# POWER_SUPPLY.net
KiCad netlist of a schematic drawn in Altium Designer
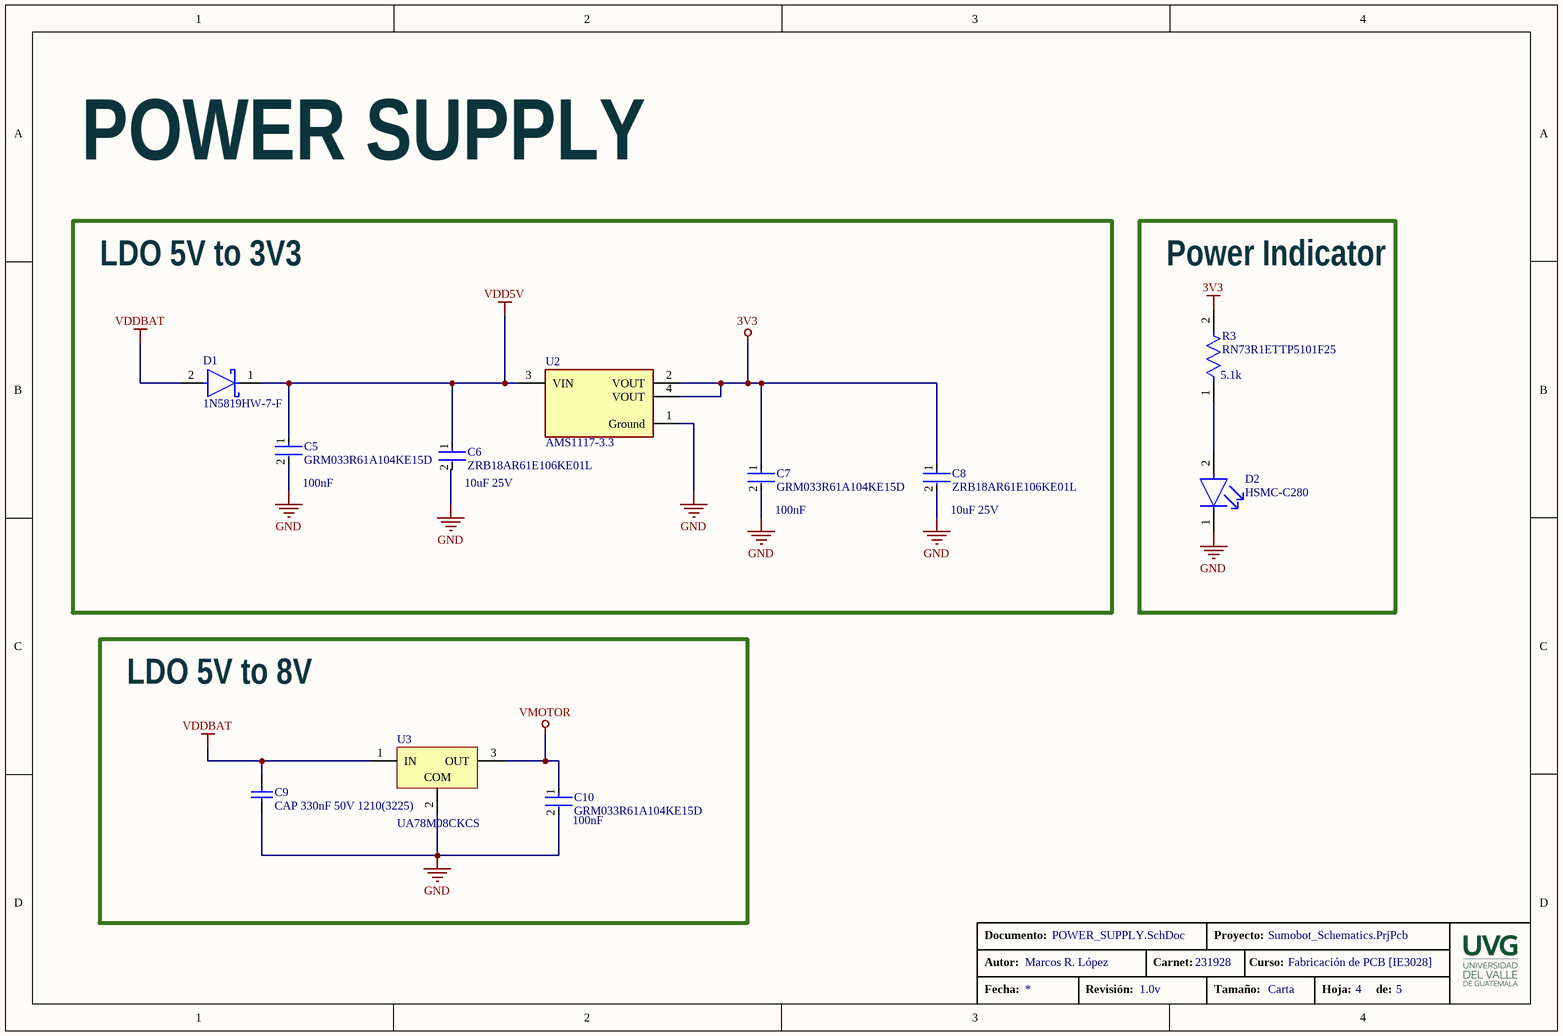
[diagram p0: POWER_SUPPLY.SchDoc]

(export (version "E")
  (design (tool "Eeschema 10.0.6"))
  (components
    (comp (ref "C5")
      (value "GRM033R61A104KE15D")
      (footprint "FP-GRM033-0_03-IPC_C")
      (description "Chip Multilayer Ceramic Capacitors for General Purpose, 0201, 0.10uF, X5R, 15%, 10%, 10V")
      (fields
        (field (name "TOLERANCE") "10%")
        (field (name "CAPACITANCE") "100nF")
        (field (name "VOLTAGE") "10V")
      )
      (libsource (lib "Altium Content Vault") (part "b4654b650e69147ec39a6b967a45e02"))
    )
    (comp (ref "C6")
      (value "ZRB18AR61E106KE01L")
      (footprint "FP-ZRB18A-0_2-MFG")
      (fields (field (name "ALTIUM_VALUE") "10uF 25V"))
      (libsource (lib "Altium Content Vault") (part "02cd4be3c70576c341d710602a673aa"))
    )
    (comp (ref "C7")
      (value "GRM033R61A104KE15D")
      (footprint "FP-GRM033-0_03-IPC_C")
      (description "Chip Multilayer Ceramic Capacitors for General Purpose, 0201, 0.10uF, X5R, 15%, 10%, 10V")
      (fields
        (field (name "TOLERANCE") "10%")
        (field (name "CAPACITANCE") "100nF")
        (field (name "VOLTAGE") "10V")
      )
      (libsource (lib "Altium Content Vault") (part "b4654b650e69147ec39a6b967a45e02"))
    )
    (comp (ref "C8")
      (value "ZRB18AR61E106KE01L")
      (footprint "FP-ZRB18A-0_2-MFG")
      (fields (field (name "ALTIUM_VALUE") "10uF 25V"))
      (libsource (lib "Altium Content Vault") (part "02cd4be3c70576c341d710602a673aa"))
    )
    (comp (ref "C9")
      (value "CAP 330nF 50V 1210(3225)")
      (footprint "CAPC1210(3225)105_L")
      (description "CAP 330nF 50V ±10% 1210 (3225 Metric) Thickness 1.05mm SMD")
      (fields (field (name "TOLERANCE") "Â±10%"))
      (libsource (lib "Altium Content Vault") (part "CAP"))
    )
    (comp (ref "C10")
      (value "GRM033R61A104KE15D")
      (footprint "FP-GRM033-0_03-IPC_C")
      (description "Chip Multilayer Ceramic Capacitors for General Purpose, 0201, 0.10uF, X5R, 15%, 10%, 10V")
      (fields
        (field (name "TOLERANCE") "10%")
        (field (name "CAPACITANCE") "100nF")
        (field (name "VOLTAGE") "10V")
      )
      (libsource (lib "Altium Content Vault") (part "b4654b650e69147ec39a6b967a45e02"))
    )
    (comp (ref "D1")
      (value "1N5819HW-7-F")
      (footprint "FP-SOD123-IPC_A")
      (description "DIODE SCHOTTKY 40V 1A SOD123")
      (libsource (lib "Altium Content Vault") (part "1d6ec82d83fb6aee721767c19dac4b9"))
    )
    (comp (ref "D2")
      (value "HSMC-C280")
      (footprint "FP-HSMC-C280-MFG")
      (description "LED RED DIFFUSED 0402 SMD")
      (libsource (lib "Altium Content Vault") (part "8706943c75ba83719d021d2fdc84c58"))
    )
    (comp (ref "R3")
      (value "RN73R1ETTP5101F25")
      (footprint "FP-RN73R1E-IPC_C")
      (description "5.1kΩ ±1% 0.063W, 1/16W Chip Resistor 0402 (1005 Metric) Moisture Resistant Thin Film")
      (fields (field (name "ALTIUM_VALUE") "5.1k"))
      (libsource (lib "Altium Content Vault") (part "1029c3af85768c4190bb7ad29bc67b5"))
    )
    (comp (ref "U2")
      (value "AMS1117-3.3")
      (footprint "FP-AMS1117-IPC_C")
      (description "LDO Voltage Regulators 1A, 3.3V")
      (fields
        (field (name "OCTOPART") "https://octopart.com/ams1117-3.3-advanced+monolithic+systems-25899300")
        (field (name "MANUFACTURER") "Advanced Monolithic Systems")
      )
      (libsource (lib "Altium Content Vault") (part "8bdbb5f8e77002000e30dd2845d0354"))
    )
    (comp (ref "U3")
      (value "UA78M08CKCS")
      (footprint "KCS0003A")
      (fields (field (name "MANUFACTURER") "Texas Instruments"))
      (libsource (lib "Altium Content Vault") (part "TI-UA78M08KCS3"))
    )
  )
  (nets
    (net (code "1") (name "3V3") (class "Default")
      (node (ref "C7") (pin "1") (pinfunction "1_1") (pintype "passive"))
      (node (ref "C8") (pin "1") (pinfunction "1_1") (pintype "passive"))
      (node (ref "R3") (pin "2") (pinfunction "2_2") (pintype "passive"))
      (node (ref "U2") (pin "2") (pinfunction "VOUT_2") (pintype "passive"))
      (node (ref "U2") (pin "4") (pinfunction "VOUT_4") (pintype "passive"))
    )
    (net (code "2") (name "GND") (class "Default")
      (node (ref "C10") (pin "2") (pinfunction "2_2") (pintype "passive"))
      (node (ref "C5") (pin "2") (pinfunction "2_2") (pintype "passive"))
      (node (ref "C6") (pin "2") (pinfunction "2_2") (pintype "passive"))
      (node (ref "C7") (pin "2") (pinfunction "2_2") (pintype "passive"))
      (node (ref "C8") (pin "2") (pinfunction "2_2") (pintype "passive"))
      (node (ref "C9") (pin "1") (pinfunction "1_1") (pintype "passive"))
      (node (ref "D2") (pin "1") (pinfunction "C_1") (pintype "passive"))
      (node (ref "U2") (pin "1") (pinfunction "Ground_1") (pintype "power_in"))
      (node (ref "U3") (pin "2") (pinfunction "COM_2") (pintype "power_in"))
    )
    (net (code "3") (name "Net-(D2-A)") (class "Default")
      (node (ref "D2") (pin "2") (pinfunction "A_2") (pintype "passive"))
      (node (ref "R3") (pin "1") (pinfunction "1_1") (pintype "passive"))
    )
    (net (code "4") (name "VDD5V") (class "Default")
      (node (ref "C5") (pin "1") (pinfunction "1_1") (pintype "passive"))
      (node (ref "C6") (pin "1") (pinfunction "1_1") (pintype "passive"))
      (node (ref "D1") (pin "1") (pinfunction "C_1") (pintype "passive"))
      (node (ref "U2") (pin "3") (pinfunction "VIN_3") (pintype "power_in"))
    )
    (net (code "5") (name "VDDBAT") (class "Default")
      (node (ref "C9") (pin "2") (pinfunction "2_2") (pintype "passive"))
      (node (ref "D1") (pin "2") (pinfunction "A_2") (pintype "passive"))
      (node (ref "U3") (pin "1") (pinfunction "IN_1") (pintype "power_in"))
    )
    (net (code "6") (name "VMOTOR") (class "Default")
      (node (ref "C10") (pin "1") (pinfunction "1_1") (pintype "passive"))
      (node (ref "U3") (pin "3") (pinfunction "OUT_3") (pintype "power_in"))
    )
  )
)
